# SCH_plytka_prezesa_2023-10-24.net
KiCad netlist of a schematic drawn in EasyEDA
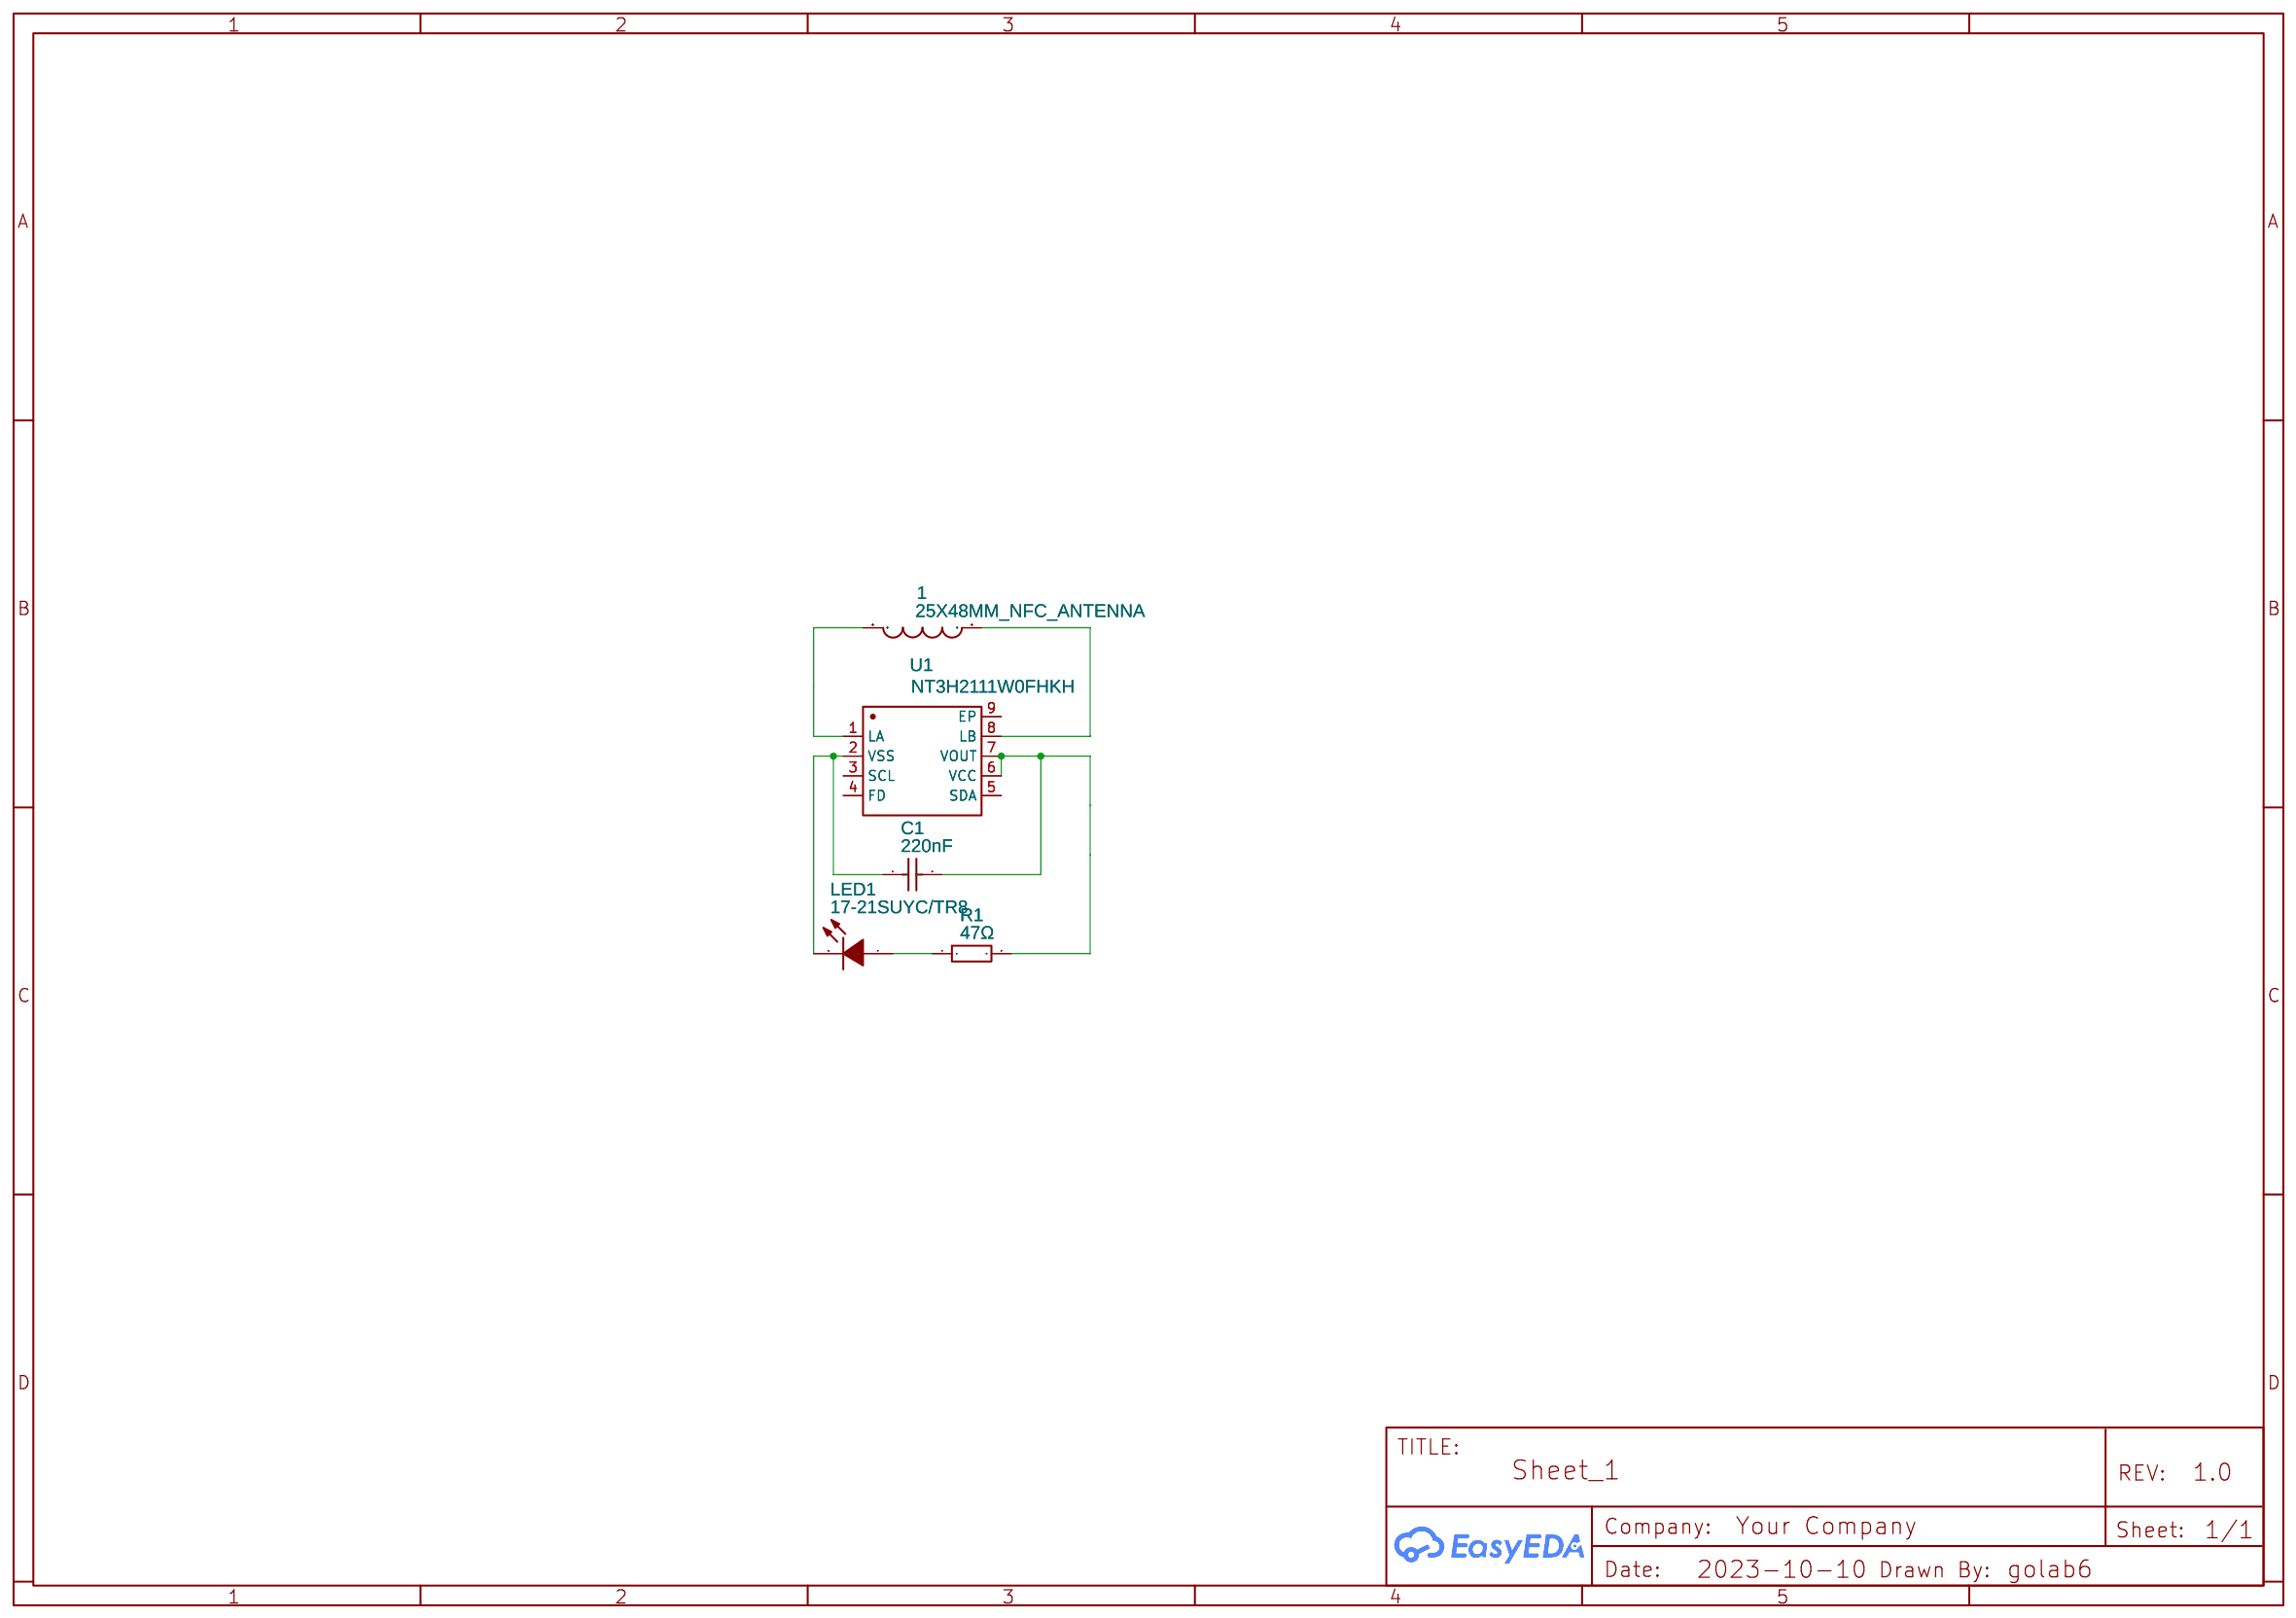
[diagram p0: schematic sheet]

(export (version "E")
  (design (tool "Eeschema 10.0.6"))
  (components
    (comp (ref "1") (value "25X48MM_NFC_ANTENNA") (libsource (lib "") (part "25X48MM_NFC_ANTENNA")))
    (comp (ref "C1")
      (value "220nF")
      (fields
        (field (name "Manufacturer Part") "CL10B224KA8NNNC")
        (field (name "Manufacturer") "SAMSUNG(三星)")
      )
      (libsource (lib "") (part "CL10B224KA8NNNC"))
    )
    (comp (ref "LED1")
      (value "17-21SUYC/TR8")
      (fields (field (name "Manufacturer Part") "KT-0805黄灯") (field (name "Manufacturer") "KENTO"))
      (libsource (lib "") (part "17-21SUYC/TR8"))
    )
    (comp (ref "R1")
      (value "47Ω")
      (fields
        (field (name "Manufacturer Part") "0603WAF470JT5E")
        (field (name "Manufacturer") "UNI-ROYAL(厚声)")
      )
      (libsource (lib "") (part "0603WAF470JT5E"))
    )
    (comp (ref "U1")
      (value "NT3H2111W0FHKH")
      (fields (field (name "Manufacturer") "NXP(恩智浦)"))
      (libsource (lib "") (part "NT3H2111W0FHKH"))
    )
  )
  (nets
    (net (code "1") (name "Net-(LED1-+)") (class "Default")
      (node (ref "LED1") (pin "1") (pinfunction "+_1") (pintype "unspecified"))
      (node (ref "R1") (pin "1") (pinfunction "1_1") (pintype "input"))
    )
    (net (code "2") (name "Net-(LED1--)") (class "Default")
      (node (ref "C1") (pin "1") (pinfunction "1_1") (pintype "input"))
      (node (ref "LED1") (pin "2") (pinfunction "-_2") (pintype "unspecified"))
      (node (ref "U1") (pin "2") (pinfunction "VSS_2") (pintype "unspecified"))
    )
    (net (code "3") (name "Net-(U1-LA)") (class "Default")
      (node (ref "1") (pin "P$2") (pinfunction "P$2_P$2") (pintype "bidirectional"))
      (node (ref "U1") (pin "1") (pinfunction "LA_1") (pintype "unspecified"))
    )
    (net (code "4") (name "Net-(U1-LB)") (class "Default")
      (node (ref "1") (pin "P$1") (pinfunction "P$1_P$1") (pintype "bidirectional"))
      (node (ref "U1") (pin "8") (pinfunction "LB_8") (pintype "unspecified"))
    )
    (net (code "5") (name "Net-(U1-VCC)") (class "Default")
      (node (ref "C1") (pin "2") (pinfunction "2_2") (pintype "input"))
      (node (ref "R1") (pin "2") (pinfunction "2_2") (pintype "input"))
      (node (ref "U1") (pin "6") (pinfunction "VCC_6") (pintype "unspecified"))
      (node (ref "U1") (pin "7") (pinfunction "VOUT_7") (pintype "unspecified"))
    )
    (net (code "6") (name "unconnected-(U1-EP-Pad9)") (class "Default")
      (node (ref "U1") (pin "9") (pinfunction "EP_9") (pintype "unspecified"))
    )
    (net (code "7") (name "unconnected-(U1-FD-Pad4)") (class "Default")
      (node (ref "U1") (pin "4") (pinfunction "FD_4") (pintype "unspecified"))
    )
    (net (code "8") (name "unconnected-(U1-SCL-Pad3)") (class "Default")
      (node (ref "U1") (pin "3") (pinfunction "SCL_3") (pintype "unspecified"))
    )
    (net (code "9") (name "unconnected-(U1-SDA-Pad5)") (class "Default")
      (node (ref "U1") (pin "5") (pinfunction "SDA_5") (pintype "unspecified"))
    )
  )
)
